# barra_sec_secundaria.net
KiCad netlist of a schematic drawn in Altium Designer
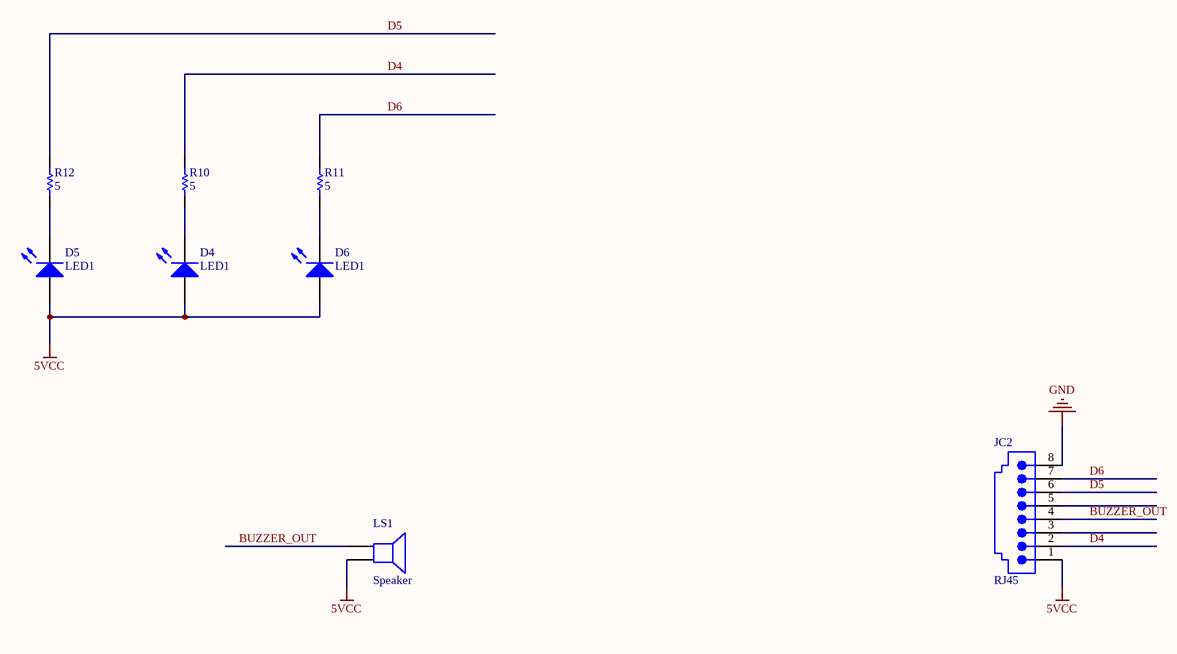
[diagram p0: barra_sec_secundaria.SchDoc]

(export (version "E")
  (design (tool "Eeschema 10.0.6"))
  (components
    (comp (ref "D4")
      (value "LED1")
      (footprint "LED5MM RED")
      (description "Typical RED GaAs LED")
      (fields (field (name "PUBLISHER") "Altium Limited"))
      (libsource (lib "Miscellaneous Devices") (part "LED1"))
    )
    (comp (ref "D5")
      (value "LED1")
      (footprint "LED5MM RED")
      (description "Typical RED GaAs LED")
      (fields (field (name "PUBLISHER") "Altium Limited"))
      (libsource (lib "Miscellaneous Devices") (part "LED1"))
    )
    (comp (ref "D6")
      (value "LED1")
      (footprint "LED5MM RED")
      (description "Typical RED GaAs LED")
      (fields (field (name "PUBLISHER") "Altium Limited"))
      (libsource (lib "Miscellaneous Devices") (part "LED1"))
    )
    (comp (ref "JC2")
      (value "RJ45")
      (footprint "15-43-6233")
      (description "Right Angle, Standard Profile, RJ45-Keyed, Flange Mount PCB Jack")
      (fields (field (name "PUBLISHER") "Altium Limited"))
      (libsource (lib "Molex Modular Jack Right Angle") (part "15-43-6233"))
    )
    (comp (ref "LS1")
      (value "Speaker")
      (footprint "C100UFA")
      (description "Loudspeaker")
      (fields (field (name "PUBLISHER") "Altium Limited"))
      (libsource (lib "Miscellaneous Devices") (part "Speaker"))
    )
    (comp (ref "R10")
      (value "5")
      (footprint "AXIAL-0.3")
      (description "Resistor")
      (fields (field (name "Comment") "Res") (field (name "PUBLISHER") "Altium Limited"))
      (libsource (lib "Miscellaneous Devices") (part "Res1"))
    )
    (comp (ref "R11")
      (value "5")
      (footprint "AXIAL-0.3")
      (description "Resistor")
      (fields (field (name "Comment") "Res") (field (name "PUBLISHER") "Altium Limited"))
      (libsource (lib "Miscellaneous Devices") (part "Res1"))
    )
    (comp (ref "R12")
      (value "5")
      (footprint "AXIAL-0.3")
      (description "Resistor")
      (fields (field (name "Comment") "Res") (field (name "PUBLISHER") "Altium Limited"))
      (libsource (lib "Miscellaneous Devices") (part "Res1"))
    )
  )
  (nets
    (net (code "1") (name "/BUZZER_OUT") (class "Default")
      (node (ref "JC2") (pin "4") (pinfunction "4_4") (pintype "passive"))
      (node (ref "LS1") (pin "1") (pinfunction "1_1") (pintype "passive"))
    )
    (net (code "2") (name "/D4") (class "Default")
      (node (ref "JC2") (pin "2") (pinfunction "2_2") (pintype "passive"))
      (node (ref "R10") (pin "2") (pinfunction "2_2") (pintype "passive"))
    )
    (net (code "3") (name "/D5") (class "Default")
      (node (ref "JC2") (pin "6") (pinfunction "6_6") (pintype "passive"))
      (node (ref "R12") (pin "2") (pinfunction "2_2") (pintype "passive"))
    )
    (net (code "4") (name "/D6") (class "Default")
      (node (ref "JC2") (pin "7") (pinfunction "7_7") (pintype "passive"))
      (node (ref "R11") (pin "2") (pinfunction "2_2") (pintype "passive"))
    )
    (net (code "5") (name "5VCC") (class "Default")
      (node (ref "D4") (pin "1") (pinfunction "A_1") (pintype "passive"))
      (node (ref "D5") (pin "1") (pinfunction "A_1") (pintype "passive"))
      (node (ref "D6") (pin "1") (pinfunction "A_1") (pintype "passive"))
      (node (ref "JC2") (pin "1") (pinfunction "1_1") (pintype "passive"))
      (node (ref "LS1") (pin "2") (pinfunction "2_2") (pintype "passive"))
    )
    (net (code "6") (name "GND") (class "Default")
      (node (ref "JC2") (pin "8") (pinfunction "8_8") (pintype "passive"))
    )
    (net (code "7") (name "Net-(D4-K)") (class "Default")
      (node (ref "D4") (pin "2") (pinfunction "K_2") (pintype "passive"))
      (node (ref "R10") (pin "1") (pinfunction "1_1") (pintype "passive"))
    )
    (net (code "8") (name "Net-(D5-K)") (class "Default")
      (node (ref "D5") (pin "2") (pinfunction "K_2") (pintype "passive"))
      (node (ref "R12") (pin "1") (pinfunction "1_1") (pintype "passive"))
    )
    (net (code "9") (name "Net-(D6-K)") (class "Default")
      (node (ref "D6") (pin "2") (pinfunction "K_2") (pintype "passive"))
      (node (ref "R11") (pin "1") (pinfunction "1_1") (pintype "passive"))
    )
    (net (code "10") (name "unconnected-(JC2-Pad3)") (class "Default")
      (node (ref "JC2") (pin "3") (pinfunction "3_3") (pintype "passive"))
    )
    (net (code "11") (name "unconnected-(JC2-Pad5)") (class "Default")
      (node (ref "JC2") (pin "5") (pinfunction "5_5") (pintype "passive"))
    )
  )
)
